# Sheet2-USB.net
KiCad netlist of a schematic drawn in Altium Designer
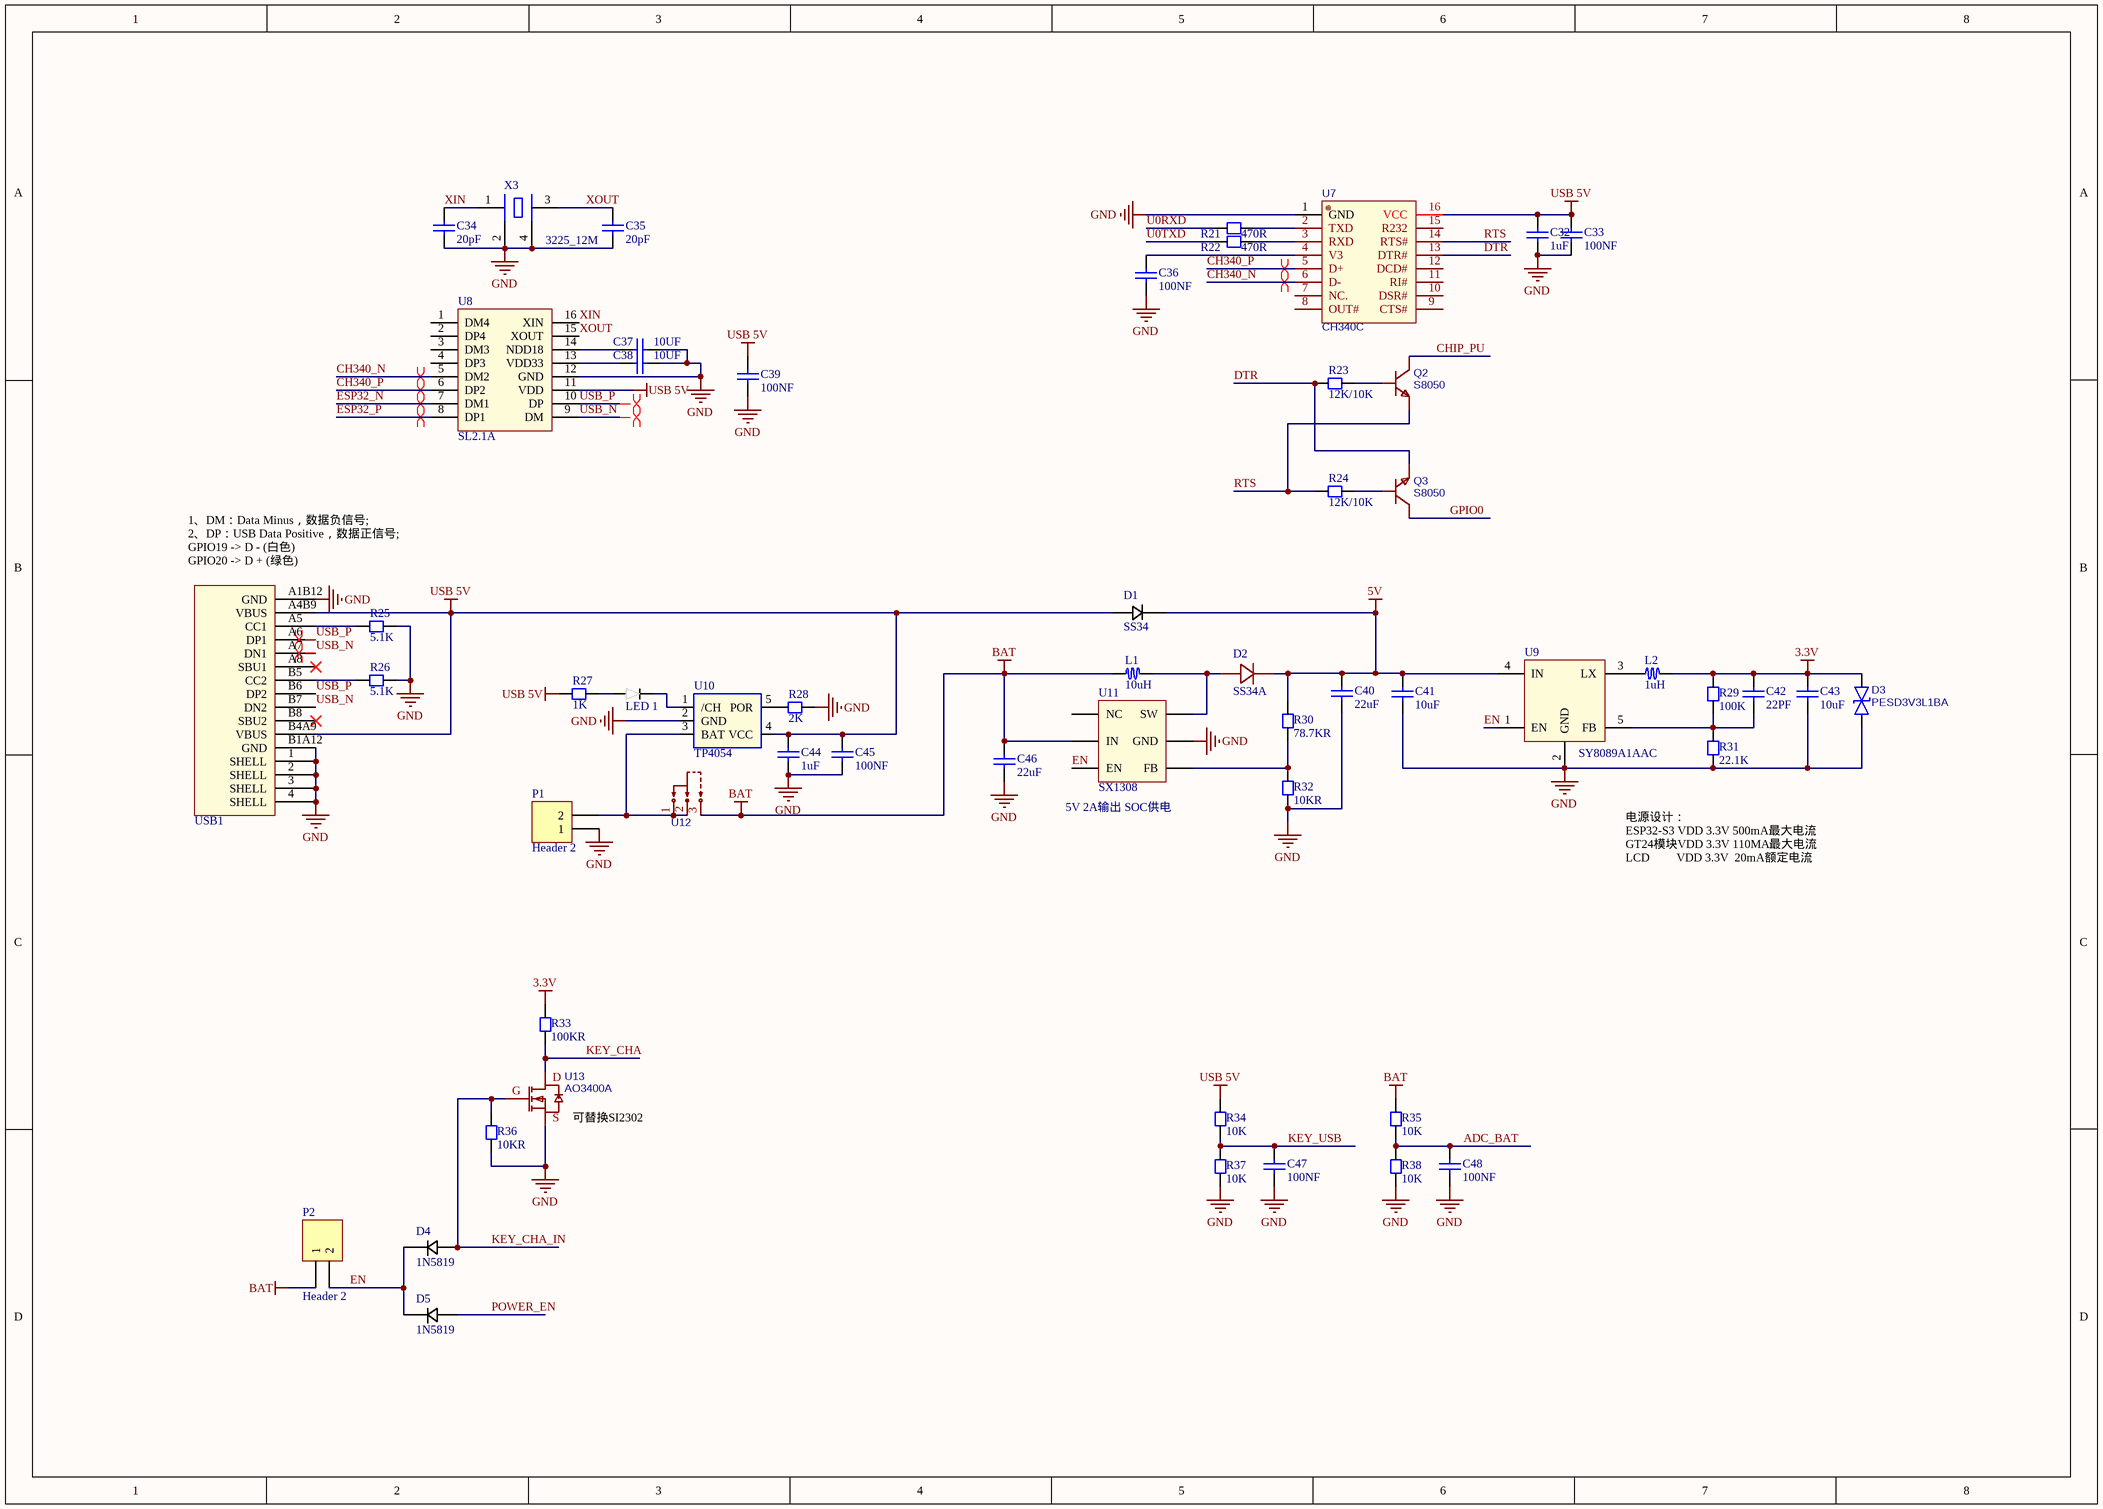
[diagram p0: Sheet2-USB.SchDoc]

(export (version "E")
  (design (tool "Eeschema 10.0.6"))
  (components
    (comp (ref "C32")
      (value "1uF")
      (footprint "CC1608-0603")
      (description "0603封装的电容")
      (fields (field (name "PUBLISHER") "Altium Limited"))
      (libsource (lib "base") (part "Cap Chip 0603"))
    )
    (comp (ref "C33")
      (value "100NF")
      (footprint "CC1608-0603")
      (description "0603封装的电容")
      (fields (field (name "PUBLISHER") "Altium Limited"))
      (libsource (lib "base") (part "Cap Chip 0603"))
    )
    (comp (ref "C34")
      (value "20pF")
      (footprint "CC1608-0603")
      (description "0603封装的电容")
      (fields (field (name "PUBLISHER") "Altium Limited"))
      (libsource (lib "base") (part "Cap Chip 0603"))
    )
    (comp (ref "C35")
      (value "20pF")
      (footprint "CC1608-0603")
      (description "0603封装的电容")
      (fields (field (name "PUBLISHER") "Altium Limited"))
      (libsource (lib "base") (part "Cap Chip 0603"))
    )
    (comp (ref "C36")
      (value "100NF")
      (footprint "CC1608-0603")
      (description "0603封装的电容")
      (fields (field (name "PUBLISHER") "Altium Limited"))
      (libsource (lib "base") (part "Cap Chip 0603"))
    )
    (comp (ref "C37")
      (value "10UF")
      (footprint "CC1608-0603")
      (description "0603封装的电容")
      (fields (field (name "PUBLISHER") "Altium Limited"))
      (libsource (lib "base") (part "Cap Chip 0603"))
    )
    (comp (ref "C38")
      (value "10UF")
      (footprint "CC1608-0603")
      (description "0603封装的电容")
      (fields (field (name "PUBLISHER") "Altium Limited"))
      (libsource (lib "base") (part "Cap Chip 0603"))
    )
    (comp (ref "C39")
      (value "100NF")
      (footprint "CC1608-0603")
      (description "0603封装的电容")
      (fields (field (name "PUBLISHER") "Altium Limited"))
      (libsource (lib "base") (part "Cap Chip 0603"))
    )
    (comp (ref "C40")
      (value "22uF")
      (footprint "CC1608-0603")
      (description "贴片电容")
      (libsource (lib "tianxiaohua_Schlib") (part "Chip capacitor"))
    )
    (comp (ref "C41")
      (value "10uF")
      (footprint "CC1608-0603")
      (description "0603封装的电容")
      (fields (field (name "PUBLISHER") "Altium Limited"))
      (libsource (lib "base") (part "Cap Chip 0603"))
    )
    (comp (ref "C42")
      (value "22PF")
      (footprint "CC1608-0603")
      (description "0603封装的电容")
      (fields (field (name "PUBLISHER") "Altium Limited"))
      (libsource (lib "base") (part "Cap Chip 0603"))
    )
    (comp (ref "C43")
      (value "10uF")
      (footprint "CC1608-0603")
      (description "0603封装的电容")
      (fields (field (name "PUBLISHER") "Altium Limited"))
      (libsource (lib "base") (part "Cap Chip 0603"))
    )
    (comp (ref "C44")
      (value "1uF")
      (footprint "CC1608-0603")
      (description "0603封装的电容")
      (fields (field (name "PUBLISHER") "Altium Limited"))
      (libsource (lib "base") (part "Cap Chip 0603"))
    )
    (comp (ref "C45")
      (value "100NF")
      (footprint "CC1608-0603")
      (description "0603封装的电容")
      (fields (field (name "PUBLISHER") "Altium Limited"))
      (libsource (lib "base") (part "Cap Chip 0603"))
    )
    (comp (ref "C46")
      (value "22uF")
      (footprint "CC1608-0603")
      (description "0603封装的电容")
      (fields (field (name "PUBLISHER") "Altium Limited"))
      (libsource (lib "base") (part "Cap Chip 0603"))
    )
    (comp (ref "C47")
      (value "100NF")
      (footprint "CC1608-0603")
      (description "0603封装的电容")
      (fields (field (name "PUBLISHER") "Altium Limited"))
      (libsource (lib "base") (part "Cap Chip 0603"))
    )
    (comp (ref "C48")
      (value "100NF")
      (footprint "CC1608-0603")
      (description "0603封装的电容")
      (fields (field (name "PUBLISHER") "Altium Limited"))
      (libsource (lib "base") (part "Cap Chip 0603"))
    )
    (comp (ref "D1")
      (value "SS34")
      (footprint "DO-214 AA")
      (description "肖特基二极管")
      (libsource (lib "transistor") (part "SS34"))
    )
    (comp (ref "D2")
      (value "SS34A")
      (footprint "DO-214 AA SMB")
      (description "大电流肖特基二极管，5A/40V")
      (libsource (lib "tianxiaohua_Schlib") (part "SS34A"))
    )
    (comp (ref "D3")
      (value "PESD3V3L1BA")
      (footprint "SOD-323")
      (description "SOD-323 3.3V 双向ESD防静电二极管保护芯片")
      (fields (field (name "MANUFACTURER") "MDD") (field (name "MANUFACTURER PART") "SMAJ6.5CA"))
      (libsource (lib "transistor") (part "PESD3V3L1BA"))
    )
    (comp (ref "D4")
      (value "1N5819")
      (footprint "SOD-323_L1.8-W1.3-LS2.5-RD")
      (description "肖特基二极管")
      (libsource (lib "transistor") (part "1N5819"))
    )
    (comp (ref "D5")
      (value "1N5819")
      (footprint "SOD-323_L1.8-W1.3-LS2.5-RD")
      (description "肖特基二极管")
      (libsource (lib "transistor") (part "1N5819"))
    )
    (comp (ref "L1")
      (value "10uH")
      (footprint "Inductor-6045")
      (description "6045封装 线绕SMD功率电感")
      (libsource (lib "base") (part "Inductor-6045"))
    )
    (comp (ref "L2")
      (value "1uH")
      (footprint "Inductor-4018")
      (description "贴片电感 1206封装")
      (libsource (lib "base") (part "Inductor-4018"))
    )
    (comp (ref "LED 1") (value "LED 0603") (footprint "LED 0603") (libsource (lib "base") (part "LED 0603")))
    (comp (ref "P1")
      (value "Header 2")
      (footprint "HX2.54-2")
      (description "Header, 2-Pin")
      (fields (field (name "PUBLISHER") "Altium Limited"))
      (libsource (lib "Connectors") (part "Header 2"))
    )
    (comp (ref "P2")
      (value "Header 2")
      (footprint "HDR1X2")
      (description "Header, 2-Pin")
      (fields (field (name "PUBLISHER") "Altium Limited"))
      (libsource (lib "") (part "Header 2_1"))
    )
    (comp (ref "Q2")
      (value "S8050")
      (footprint "SOT-23")
      (fields (field (name "MANUFACTURER") "SALLTECH(萨瑞)") (field (name "CONTRIBUTOR") "lcsc"))
      (libsource (lib "transistor") (part "S8050"))
    )
    (comp (ref "Q3")
      (value "S8050")
      (footprint "SOT-23")
      (fields (field (name "MANUFACTURER") "SALLTECH(萨瑞)") (field (name "CONTRIBUTOR") "lcsc"))
      (libsource (lib "transistor") (part "S8050"))
    )
    (comp (ref "R21")
      (value "470R")
      (footprint "CR1608-0603")
      (description "0603封装电阻")
      (fields (field (name "PUBLISHER") "Altium Limited"))
      (libsource (lib "") (part "Resistor Chip 0603_2"))
    )
    (comp (ref "R22")
      (value "470R")
      (footprint "CR1608-0603")
      (description "0603封装电阻")
      (fields (field (name "PUBLISHER") "Altium Limited"))
      (libsource (lib "") (part "Resistor Chip 0603_2"))
    )
    (comp (ref "R23")
      (value "12K/10K")
      (footprint "CR1608-0603")
      (description "0603封装电阻")
      (fields (field (name "PUBLISHER") "Altium Limited"))
      (libsource (lib "") (part "Resistor Chip 0603_1"))
    )
    (comp (ref "R24")
      (value "12K/10K")
      (footprint "CR1608-0603")
      (description "0603封装电阻")
      (fields (field (name "PUBLISHER") "Altium Limited"))
      (libsource (lib "base") (part "Resistor Chip 0603"))
    )
    (comp (ref "R25")
      (value "5.1K")
      (footprint "CR1608-0603")
      (description "0603封装电阻")
      (fields (field (name "PUBLISHER") "Altium Limited"))
      (libsource (lib "") (part "Resistor Chip 0603_2"))
    )
    (comp (ref "R26")
      (value "5.1K")
      (footprint "CR1608-0603")
      (description "0603封装电阻")
      (fields (field (name "PUBLISHER") "Altium Limited"))
      (libsource (lib "") (part "Resistor Chip 0603_2"))
    )
    (comp (ref "R27")
      (value "1K")
      (footprint "CR1608-0603")
      (description "0603封装电阻")
      (fields (field (name "PUBLISHER") "Altium Limited"))
      (libsource (lib "") (part "Resistor Chip 0603_1"))
    )
    (comp (ref "R28")
      (value "2K")
      (footprint "CR1608-0603")
      (description "0603封装电阻")
      (fields (field (name "PUBLISHER") "Altium Limited"))
      (libsource (lib "") (part "Resistor Chip 0603_1"))
    )
    (comp (ref "R29")
      (value "100K")
      (footprint "CR1608-0603")
      (description "0603封装电阻")
      (fields (field (name "PUBLISHER") "Altium Limited"))
      (libsource (lib "") (part "Resistor Chip 0603_3"))
    )
    (comp (ref "R30")
      (value "78.7KR")
      (footprint "CR1608-0603")
      (description "贴片电阻")
      (libsource (lib "tianxiaohua_Schlib") (part "Chip resistor"))
    )
    (comp (ref "R31")
      (value "22.1K")
      (footprint "CR1608-0603")
      (description "0603封装电阻")
      (fields (field (name "PUBLISHER") "Altium Limited"))
      (libsource (lib "") (part "Resistor Chip 0603_3"))
    )
    (comp (ref "R32")
      (value "10KR")
      (footprint "CR1608-0603")
      (description "贴片电阻")
      (libsource (lib "tianxiaohua_Schlib") (part "Chip resistor"))
    )
    (comp (ref "R33")
      (value "100KR")
      (footprint "CR1608-0603")
      (description "贴片电阻")
      (libsource (lib "tianxiaohua_Schlib") (part "Chip resistor"))
    )
    (comp (ref "R34")
      (value "10K")
      (footprint "CR1608-0603")
      (description "0603封装电阻")
      (fields (field (name "PUBLISHER") "Altium Limited"))
      (libsource (lib "base") (part "Resistor Chip 0603"))
    )
    (comp (ref "R35")
      (value "10K")
      (footprint "CR1608-0603")
      (description "0603封装电阻")
      (fields (field (name "PUBLISHER") "Altium Limited"))
      (libsource (lib "base") (part "Resistor Chip 0603"))
    )
    (comp (ref "R36")
      (value "10KR")
      (footprint "CR1608-0603")
      (description "贴片电阻")
      (libsource (lib "tianxiaohua_Schlib") (part "Chip resistor"))
    )
    (comp (ref "R37")
      (value "10K")
      (footprint "CR1608-0603")
      (description "0603封装电阻")
      (fields (field (name "PUBLISHER") "Altium Limited"))
      (libsource (lib "base") (part "Resistor Chip 0603"))
    )
    (comp (ref "R38")
      (value "10K")
      (footprint "CR1608-0603")
      (description "0603封装电阻")
      (fields (field (name "PUBLISHER") "Altium Limited"))
      (libsource (lib "base") (part "Resistor Chip 0603"))
    )
    (comp (ref "U7")
      (value "CH340C")
      (footprint "SOP-16")
      (fields (field (name "MANUFACTURER") "WCH(南京沁恒)"))
      (libsource (lib "PB-Chip") (part "CH340C"))
    )
    (comp (ref "U8")
      (value "SL2.1A")
      (footprint "SOP-16")
      (description "USB HUB 四拓展")
      (libsource (lib "sensor") (part "SL2.1A"))
    )
    (comp (ref "U9")
      (value "SY8089A1AAC")
      (footprint "SOT23-5")
      (libsource (lib "power-chip") (part "SY8089A1AAC"))
    )
    (comp (ref "U10")
      (value "TP4054")
      (footprint "SOT23-5")
      (description "迷你充电IC SOT-23-5")
      (libsource (lib "power-chip") (part "TP4054"))
    )
    (comp (ref "U11")
      (value "SX1308")
      (footprint "SOT23-6")
      (description "SOT23-6 升压芯片")
      (libsource (lib "power-chip") (part "SX1308"))
    )
    (comp (ref "U12")
      (value "HX SS12D10G4")
      (footprint "SW-TH_3P-SS12D06")
      (fields (field (name "BOM_SUPPLIER PART") "C5149841") (field (name "CONTRIBUTOR") "lcsc"))
      (libsource (lib "base") (part "SW-TH_3P-SS12D06"))
    )
    (comp (ref "U13")
      (value "AO3400A")
      (footprint "SOT-23")
      (description "UMW AO3400A SOT-23 30V/5.8A N沟道 MOS(场效应管)芯片")
      (fields
        (field (name "MANUFACTURER") "ElecSuper(静芯微）")
        (field (name "MANUFACTURER PART") "AO3401A")
        (field (name "CONTRIBUTOR") "lcsc")
      )
      (libsource (lib "transistor") (part "AO3400A"))
    )
    (comp (ref "USB1")
      (value "Tpye-c 16P")
      (footprint "TYPE-C 16P")
      (description "16P 封装的TYPE -c接口 4固定插脚 双向")
      (libsource (lib "Connectors") (part "Tpye-c 16P"))
    )
    (comp (ref "X3")
      (value "3225_12M")
      (footprint "XTAL-3225")
      (description "3225封装的晶振")
      (libsource (lib "base") (part "XTAL 3225"))
    )
  )
  (nets
    (net (code "1") (name "/ADC_BAT") (class "Default")
      (node (ref "C48") (pin "2") (pinfunction "2_2") (pintype "passive"))
      (node (ref "R35") (pin "1") (pinfunction "1_1") (pintype "passive"))
      (node (ref "R38") (pin "2") (pinfunction "2_2") (pintype "passive"))
    )
    (net (code "2") (name "/CH340_N") (class "Default")
      (node (ref "U7") (pin "6") (pinfunction "D-_6") (pintype "passive"))
      (node (ref "U8") (pin "5") (pinfunction "DM2_5") (pintype "passive"))
    )
    (net (code "3") (name "/CH340_P") (class "Default")
      (node (ref "U7") (pin "5") (pinfunction "D+_5") (pintype "passive"))
      (node (ref "U8") (pin "6") (pinfunction "DP2_6") (pintype "passive"))
    )
    (net (code "4") (name "/CHIP_PU") (class "Default")
      (node (ref "Q2") (pin "3") (pinfunction "C_3") (pintype "passive"))
    )
    (net (code "5") (name "/DTR") (class "Default")
      (node (ref "Q3") (pin "2") (pinfunction "E_2") (pintype "passive"))
      (node (ref "R23") (pin "1") (pinfunction "1_1") (pintype "passive"))
      (node (ref "U7") (pin "13") (pinfunction "DTR#_13") (pintype "passive"))
    )
    (net (code "6") (name "/EN") (class "Default")
      (node (ref "D4") (pin "1") (pinfunction "1_1") (pintype "passive"))
      (node (ref "D5") (pin "1") (pinfunction "1_1") (pintype "passive"))
      (node (ref "P2") (pin "2") (pinfunction "2_2") (pintype "passive"))
      (node (ref "U11") (pin "4") (pinfunction "EN_4") (pintype "passive"))
      (node (ref "U9") (pin "1") (pinfunction "EN_1") (pintype "passive"))
    )
    (net (code "7") (name "/ESP32_N") (class "Default")
      (node (ref "U8") (pin "7") (pinfunction "DM1_7") (pintype "passive"))
    )
    (net (code "8") (name "/ESP32_P") (class "Default")
      (node (ref "U8") (pin "8") (pinfunction "DP1_8") (pintype "passive"))
    )
    (net (code "9") (name "/GPIO0") (class "Default")
      (node (ref "Q3") (pin "3") (pinfunction "C_3") (pintype "passive"))
    )
    (net (code "10") (name "/KEY_CHA") (class "Default")
      (node (ref "R33") (pin "1") (pinfunction "1_1") (pintype "passive"))
      (node (ref "U13") (pin "3") (pinfunction "D_3") (pintype "passive"))
    )
    (net (code "11") (name "/KEY_CHA_IN") (class "Default")
      (node (ref "D4") (pin "2") (pinfunction "2_2") (pintype "passive"))
      (node (ref "R36") (pin "2") (pinfunction "2_2") (pintype "passive"))
      (node (ref "U13") (pin "1") (pinfunction "G_1") (pintype "passive"))
    )
    (net (code "12") (name "/KEY_USB") (class "Default")
      (node (ref "C47") (pin "2") (pinfunction "2_2") (pintype "passive"))
      (node (ref "R34") (pin "1") (pinfunction "1_1") (pintype "passive"))
      (node (ref "R37") (pin "2") (pinfunction "2_2") (pintype "passive"))
    )
    (net (code "13") (name "/POWER_EN") (class "Default")
      (node (ref "D5") (pin "2") (pinfunction "2_2") (pintype "passive"))
    )
    (net (code "14") (name "/RTS") (class "Default")
      (node (ref "Q2") (pin "2") (pinfunction "E_2") (pintype "passive"))
      (node (ref "R24") (pin "1") (pinfunction "1_1") (pintype "passive"))
      (node (ref "U7") (pin "14") (pinfunction "RTS#_14") (pintype "passive"))
    )
    (net (code "15") (name "/U0RXD") (class "Default")
      (node (ref "R21") (pin "2") (pinfunction "2_2") (pintype "passive"))
    )
    (net (code "16") (name "/U0TXD") (class "Default")
      (node (ref "R22") (pin "2") (pinfunction "2_2") (pintype "passive"))
    )
    (net (code "17") (name "/USB_N") (class "Default")
      (node (ref "U8") (pin "9") (pinfunction "DM_9") (pintype "passive"))
      (node (ref "USB1") (pin "A7") (pinfunction "DN1_A7") (pintype "power_in"))
      (node (ref "USB1") (pin "B7") (pinfunction "DN2_B7") (pintype "power_in"))
    )
    (net (code "18") (name "/USB_P") (class "Default")
      (node (ref "U8") (pin "10") (pinfunction "DP_10") (pintype "passive"))
      (node (ref "USB1") (pin "A6") (pinfunction "DP1_A6") (pintype "power_in"))
      (node (ref "USB1") (pin "B6") (pinfunction "DP2_B6") (pintype "power_in"))
    )
    (net (code "19") (name "/XIN") (class "Default")
      (node (ref "C34") (pin "2") (pinfunction "2_2") (pintype "passive"))
      (node (ref "U8") (pin "16") (pinfunction "XIN_16") (pintype "passive"))
      (node (ref "X3") (pin "1") (pinfunction "OSC1_1") (pintype "passive"))
    )
    (net (code "20") (name "/XOUT") (class "Default")
      (node (ref "C35") (pin "2") (pinfunction "2_2") (pintype "passive"))
      (node (ref "U8") (pin "15") (pinfunction "XOUT_15") (pintype "passive"))
      (node (ref "X3") (pin "3") (pinfunction "OSC2_3") (pintype "passive"))
    )
    (net (code "21") (name "3.3V") (class "Default")
      (node (ref "C42") (pin "2") (pinfunction "2_2") (pintype "passive"))
      (node (ref "C43") (pin "2") (pinfunction "2_2") (pintype "passive"))
      (node (ref "D3") (pin "1") (pinfunction "1_1") (pintype "passive"))
      (node (ref "L2") (pin "2") (pinfunction "2_2") (pintype "passive"))
      (node (ref "R29") (pin "1") (pinfunction "1_1") (pintype "passive"))
      (node (ref "R33") (pin "2") (pinfunction "2_2") (pintype "passive"))
    )
    (net (code "22") (name "5V") (class "Default")
      (node (ref "C40") (pin "1") (pinfunction "1_1") (pintype "passive"))
      (node (ref "C41") (pin "2") (pinfunction "2_2") (pintype "passive"))
      (node (ref "D1") (pin "1") (pinfunction "K_1") (pintype "passive"))
      (node (ref "D2") (pin "1") (pinfunction "C_1") (pintype "passive"))
      (node (ref "R30") (pin "2") (pinfunction "2_2") (pintype "passive"))
      (node (ref "U9") (pin "4") (pinfunction "IN_4") (pintype "passive"))
    )
    (net (code "23") (name "BAT") (class "Default")
      (node (ref "C46") (pin "2") (pinfunction "2_2") (pintype "passive"))
      (node (ref "L1") (pin "1") (pinfunction "1_1") (pintype "passive"))
      (node (ref "P2") (pin "1") (pinfunction "1_1") (pintype "passive"))
      (node (ref "R35") (pin "2") (pinfunction "2_2") (pintype "passive"))
      (node (ref "U11") (pin "5") (pinfunction "IN_5") (pintype "passive"))
      (node (ref "U12") (pin "3") (pinfunction "3_3") (pintype "passive"))
    )
    (net (code "24") (name "GND") (class "Default")
      (node (ref "C32") (pin "1") (pinfunction "1_1") (pintype "passive"))
      (node (ref "C33") (pin "1") (pinfunction "1_1") (pintype "passive"))
      (node (ref "C34") (pin "1") (pinfunction "1_1") (pintype "passive"))
      (node (ref "C35") (pin "1") (pinfunction "1_1") (pintype "passive"))
      (node (ref "C36") (pin "1") (pinfunction "1_1") (pintype "passive"))
      (node (ref "C37") (pin "1") (pinfunction "1_1") (pintype "passive"))
      (node (ref "C38") (pin "1") (pinfunction "1_1") (pintype "passive"))
      (node (ref "C39") (pin "1") (pinfunction "1_1") (pintype "passive"))
      (node (ref "C40") (pin "2") (pinfunction "2_2") (pintype "passive"))
      (node (ref "C41") (pin "1") (pinfunction "1_1") (pintype "passive"))
      (node (ref "C43") (pin "1") (pinfunction "1_1") (pintype "passive"))
      (node (ref "C44") (pin "1") (pinfunction "1_1") (pintype "passive"))
      (node (ref "C45") (pin "1") (pinfunction "1_1") (pintype "passive"))
      (node (ref "C46") (pin "1") (pinfunction "1_1") (pintype "passive"))
      (node (ref "C47") (pin "1") (pinfunction "1_1") (pintype "passive"))
      (node (ref "C48") (pin "1") (pinfunction "1_1") (pintype "passive"))
      (node (ref "D3") (pin "2") (pinfunction "2_2") (pintype "passive"))
      (node (ref "P1") (pin "1") (pinfunction "1_1") (pintype "passive"))
      (node (ref "R25") (pin "1") (pinfunction "1_1") (pintype "passive"))
      (node (ref "R26") (pin "1") (pinfunction "1_1") (pintype "passive"))
      (node (ref "R28") (pin "2") (pinfunction "2_2") (pintype "passive"))
      (node (ref "R31") (pin "2") (pinfunction "2_2") (pintype "passive"))
      (node (ref "R32") (pin "1") (pinfunction "1_1") (pintype "passive"))
      (node (ref "R36") (pin "1") (pinfunction "1_1") (pintype "passive"))
      (node (ref "R37") (pin "1") (pinfunction "1_1") (pintype "passive"))
      (node (ref "R38") (pin "1") (pinfunction "1_1") (pintype "passive"))
      (node (ref "U10") (pin "2") (pinfunction "GND_2") (pintype "passive"))
      (node (ref "U11") (pin "2") (pinfunction "GND_2") (pintype "passive"))
      (node (ref "U13") (pin "2") (pinfunction "S_2") (pintype "passive"))
      (node (ref "U7") (pin "1") (pinfunction "GND_1") (pintype "passive"))
      (node (ref "U8") (pin "12") (pinfunction "GND_12") (pintype "passive"))
      (node (ref "U9") (pin "2") (pinfunction "GND_2") (pintype "passive"))
      (node (ref "USB1") (pin "1") (pinfunction "SHELL_1") (pintype "power_in"))
      (node (ref "USB1") (pin "2") (pinfunction "SHELL_2") (pintype "power_in"))
      (node (ref "USB1") (pin "3") (pinfunction "SHELL_3") (pintype "power_in"))
      (node (ref "USB1") (pin "4") (pinfunction "SHELL_4") (pintype "power_in"))
      (node (ref "USB1") (pin "A1B12") (pinfunction "GND_A1B12") (pintype "power_in"))
      (node (ref "USB1") (pin "B1A12") (pinfunction "GND_B1A12") (pintype "power_in"))
      (node (ref "X3") (pin "2") (pinfunction "GND_2") (pintype "passive"))
      (node (ref "X3") (pin "4") (pinfunction "GND_4") (pintype "passive"))
    )
    (net (code "25") (name "Net-(D2-A)") (class "Default")
      (node (ref "D2") (pin "2") (pinfunction "A_2") (pintype "passive"))
      (node (ref "L1") (pin "2") (pinfunction "2_2") (pintype "passive"))
      (node (ref "U11") (pin "1") (pinfunction "SW_1") (pintype "passive"))
    )
    (net (code "26") (name "Net-(LED 1-Pad1)") (class "Default")
      (node (ref "LED 1") (pin "1") (pinfunction "1_1") (pintype "passive"))
      (node (ref "R27") (pin "2") (pinfunction "2_2") (pintype "passive"))
    )
    (net (code "27") (name "Net-(Q2-B)") (class "Default")
      (node (ref "Q2") (pin "1") (pinfunction "B_1") (pintype "passive"))
      (node (ref "R23") (pin "2") (pinfunction "2_2") (pintype "passive"))
    )
    (net (code "28") (name "Net-(Q3-B)") (class "Default")
      (node (ref "Q3") (pin "1") (pinfunction "B_1") (pintype "passive"))
      (node (ref "R24") (pin "2") (pinfunction "2_2") (pintype "passive"))
    )
    (net (code "29") (name "Net-(U7-RXD)") (class "Default")
      (node (ref "R22") (pin "1") (pinfunction "1_1") (pintype "passive"))
      (node (ref "U7") (pin "3") (pinfunction "RXD_3") (pintype "passive"))
    )
    (net (code "30") (name "Net-(U7-TXD)") (class "Default")
      (node (ref "R21") (pin "1") (pinfunction "1_1") (pintype "passive"))
      (node (ref "U7") (pin "2") (pinfunction "TXD_2") (pintype "passive"))
    )
    (net (code "31") (name "Net-(U7-V3)") (class "Default")
      (node (ref "C36") (pin "2") (pinfunction "2_2") (pintype "passive"))
      (node (ref "U7") (pin "4") (pinfunction "V3_4") (pintype "passive"))
    )
    (net (code "32") (name "Net-(U8-NDD18)") (class "Default")
      (node (ref "C37") (pin "2") (pinfunction "2_2") (pintype "passive"))
      (node (ref "U8") (pin "14") (pinfunction "NDD18_14") (pintype "passive"))
    )
    (net (code "33") (name "Net-(U8-VDD33)") (class "Default")
      (node (ref "C38") (pin "2") (pinfunction "2_2") (pintype "passive"))
      (node (ref "U8") (pin "13") (pinfunction "VDD33_13") (pintype "passive"))
    )
    (net (code "34") (name "Net-(U9-FB)") (class "Default")
      (node (ref "C42") (pin "1") (pinfunction "1_1") (pintype "passive"))
      (node (ref "R29") (pin "2") (pinfunction "2_2") (pintype "passive"))
      (node (ref "R31") (pin "1") (pinfunction "1_1") (pintype "passive"))
      (node (ref "U9") (pin "5") (pinfunction "FB_5") (pintype "passive"))
    )
    (net (code "35") (name "Net-(U9-LX)") (class "Default")
      (node (ref "L2") (pin "1") (pinfunction "1_1") (pintype "passive"))
      (node (ref "U9") (pin "3") (pinfunction "LX_3") (pintype "passive"))
    )
    (net (code "36") (name "Net-(U10-BAT)") (class "Default")
      (node (ref "P1") (pin "2") (pinfunction "2_2") (pintype "passive"))
      (node (ref "U10") (pin "3") (pinfunction "BAT_3") (pintype "passive"))
      (node (ref "U12") (pin "1") (pinfunction "1_1") (pintype "passive"))
      (node (ref "U12") (pin "2") (pinfunction "2_2") (pintype "passive"))
    )
    (net (code "37") (name "Net-(U10-POR)") (class "Default")
      (node (ref "R28") (pin "1") (pinfunction "1_1") (pintype "passive"))
      (node (ref "U10") (pin "5") (pinfunction "POR_5") (pintype "passive"))
    )
    (net (code "38") (name "Net-(U10-{slash}CH)") (class "Default")
      (node (ref "LED 1") (pin "2") (pinfunction "2_2") (pintype "passive"))
      (node (ref "U10") (pin "1") (pinfunction "/CH_1") (pintype "passive"))
    )
    (net (code "39") (name "Net-(U11-FB)") (class "Default")
      (node (ref "R30") (pin "1") (pinfunction "1_1") (pintype "passive"))
      (node (ref "R32") (pin "2") (pinfunction "2_2") (pintype "passive"))
      (node (ref "U11") (pin "3") (pinfunction "FB_3") (pintype "passive"))
    )
    (net (code "40") (name "Net-(USB1-CC1)") (class "Default")
      (node (ref "R25") (pin "2") (pinfunction "2_2") (pintype "passive"))
      (node (ref "USB1") (pin "A5") (pinfunction "CC1_A5") (pintype "power_in"))
    )
    (net (code "41") (name "Net-(USB1-CC2)") (class "Default")
      (node (ref "R26") (pin "2") (pinfunction "2_2") (pintype "passive"))
      (node (ref "USB1") (pin "B5") (pinfunction "CC2_B5") (pintype "power_in"))
    )
    (net (code "42") (name "USB 5V") (class "Default")
      (node (ref "C32") (pin "2") (pinfunction "2_2") (pintype "passive"))
      (node (ref "C33") (pin "2") (pinfunction "2_2") (pintype "passive"))
      (node (ref "C39") (pin "2") (pinfunction "2_2") (pintype "passive"))
      (node (ref "C44") (pin "2") (pinfunction "2_2") (pintype "passive"))
      (node (ref "C45") (pin "2") (pinfunction "2_2") (pintype "passive"))
      (node (ref "D1") (pin "2") (pinfunction "A_2") (pintype "passive"))
      (node (ref "R27") (pin "1") (pinfunction "1_1") (pintype "passive"))
      (node (ref "R34") (pin "2") (pinfunction "2_2") (pintype "passive"))
      (node (ref "U10") (pin "4") (pinfunction "VCC_4") (pintype "passive"))
      (node (ref "U7") (pin "16") (pinfunction "VCC_16") (pintype "passive"))
      (node (ref "U8") (pin "11") (pinfunction "VDD_11") (pintype "passive"))
      (node (ref "USB1") (pin "A4B9") (pinfunction "VBUS_A4B9") (pintype "power_in"))
      (node (ref "USB1") (pin "B4A9") (pinfunction "VBUS_B4A9") (pintype "power_in"))
    )
    (net (code "43") (name "unconnected-(U7-CTS#-Pad9)") (class "Default")
      (node (ref "U7") (pin "9") (pinfunction "CTS#_9") (pintype "passive"))
    )
    (net (code "44") (name "unconnected-(U7-DCD#-Pad12)") (class "Default")
      (node (ref "U7") (pin "12") (pinfunction "DCD#_12") (pintype "passive"))
    )
    (net (code "45") (name "unconnected-(U7-DSR#-Pad10)") (class "Default")
      (node (ref "U7") (pin "10") (pinfunction "DSR#_10") (pintype "passive"))
    )
    (net (code "46") (name "unconnected-(U7-NC.-Pad7)") (class "Default")
      (node (ref "U7") (pin "7") (pinfunction "NC._7") (pintype "passive"))
    )
    (net (code "47") (name "unconnected-(U7-OUT#-Pad8)") (class "Default")
      (node (ref "U7") (pin "8") (pinfunction "OUT#_8") (pintype "passive"))
    )
    (net (code "48") (name "unconnected-(U7-R232-Pad15)") (class "Default")
      (node (ref "U7") (pin "15") (pinfunction "R232_15") (pintype "passive"))
    )
    (net (code "49") (name "unconnected-(U7-RI#-Pad11)") (class "Default")
      (node (ref "U7") (pin "11") (pinfunction "RI#_11") (pintype "passive"))
    )
    (net (code "50") (name "unconnected-(U8-DM3-Pad3)") (class "Default")
      (node (ref "U8") (pin "3") (pinfunction "DM3_3") (pintype "passive"))
    )
    (net (code "51") (name "unconnected-(U8-DM4-Pad1)") (class "Default")
      (node (ref "U8") (pin "1") (pinfunction "DM4_1") (pintype "passive"))
    )
    (net (code "52") (name "unconnected-(U8-DP3-Pad4)") (class "Default")
      (node (ref "U8") (pin "4") (pinfunction "DP3_4") (pintype "passive"))
    )
    (net (code "53") (name "unconnected-(U8-DP4-Pad2)") (class "Default")
      (node (ref "U8") (pin "2") (pinfunction "DP4_2") (pintype "passive"))
    )
    (net (code "54") (name "unconnected-(U11-NC-Pad6)") (class "Default")
      (node (ref "U11") (pin "6") (pinfunction "NC_6") (pintype "passive"))
    )
    (net (code "55") (name "unconnected-(USB1-SBU1-PadA8)") (class "Default")
      (node (ref "USB1") (pin "A8") (pinfunction "SBU1_A8") (pintype "power_in+no_connect"))
    )
    (net (code "56") (name "unconnected-(USB1-SBU2-PadB8)") (class "Default")
      (node (ref "USB1") (pin "B8") (pinfunction "SBU2_B8") (pintype "power_in+no_connect"))
    )
  )
)
